# LiDAR.net
KiCad netlist of a schematic drawn in Altium Designer
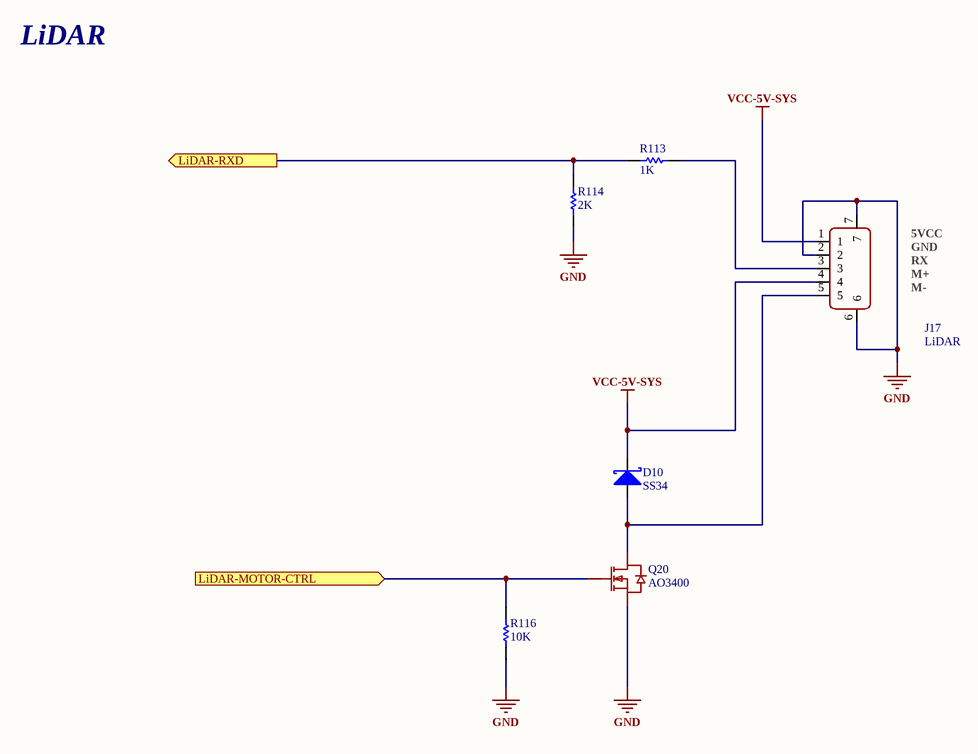
[diagram p0: LiDAR .SchDoc]

(export (version "E")
  (design (tool "Eeschema 10.0.6"))
  (components
    (comp (ref "D10") (value "SS34") (footprint "SMA") (libsource (lib "DesignLibrary") (part "DIODE-2")))
    (comp (ref "J17")
      (value "LiDAR")
      (footprint "CONN-SMD_5P-P1.25_XUNPU_WAFER-GH1.25-5PWB")
      (description "WAFER-GH1.25-5PWB")
      (libsource (lib "DesignLibrary") (part "HDRx5"))
    )
    (comp (ref "Q20")
      (value "AO3400")
      (footprint "SOT23-3D")
      (libsource (lib "DesignLibrary") (part "N-MOS-SOT23"))
    )
    (comp (ref "R113")
      (value "1K")
      (footprint "RES-0402")
      (libsource (lib "DesignLibrary") (part "Resistor-1"))
    )
    (comp (ref "R114")
      (value "2K")
      (footprint "RES-0402")
      (libsource (lib "DesignLibrary") (part "Resistor-1"))
    )
    (comp (ref "R116")
      (value "10K")
      (footprint "RES-0402")
      (libsource (lib "DesignLibrary") (part "Resistor-1"))
    )
  )
  (nets
    (net (code "1") (name "/LiDAR-MOTOR-CTRL") (class "Default")
      (node (ref "Q20") (pin "1") (pinfunction "G_1") (pintype "passive"))
      (node (ref "R116") (pin "2") (pintype "passive"))
    )
    (net (code "2") (name "/LiDAR-RXD") (class "Default")
      (node (ref "R113") (pin "1") (pintype "passive"))
      (node (ref "R114") (pin "2") (pintype "passive"))
    )
    (net (code "3") (name "GND") (class "Default")
      (node (ref "J17") (pin "2") (pinfunction "2_2") (pintype "passive"))
      (node (ref "J17") (pin "6") (pinfunction "6_6") (pintype "passive"))
      (node (ref "J17") (pin "7") (pinfunction "7_7") (pintype "passive"))
      (node (ref "Q20") (pin "2") (pinfunction "S_2") (pintype "passive"))
      (node (ref "R114") (pin "1") (pintype "passive"))
      (node (ref "R116") (pin "1") (pintype "passive"))
    )
    (net (code "4") (name "Net-(D10-A)") (class "Default")
      (node (ref "D10") (pin "1") (pinfunction "A_1") (pintype "passive"))
      (node (ref "J17") (pin "5") (pinfunction "5_5") (pintype "passive"))
      (node (ref "Q20") (pin "3") (pinfunction "D_3") (pintype "passive"))
    )
    (net (code "5") (name "Net-(J17-Pad3)") (class "Default")
      (node (ref "J17") (pin "3") (pinfunction "3_3") (pintype "passive"))
      (node (ref "R113") (pin "2") (pintype "passive"))
    )
    (net (code "6") (name "VCC-5V-SYS") (class "Default")
      (node (ref "D10") (pin "2") (pinfunction "K_2") (pintype "passive"))
      (node (ref "J17") (pin "1") (pinfunction "1_1") (pintype "passive"))
      (node (ref "J17") (pin "4") (pinfunction "4_4") (pintype "passive"))
    )
  )
)
